# tinytouchbutton_v2_0_2.net
KiCad netlist of a schematic drawn in EAGLE
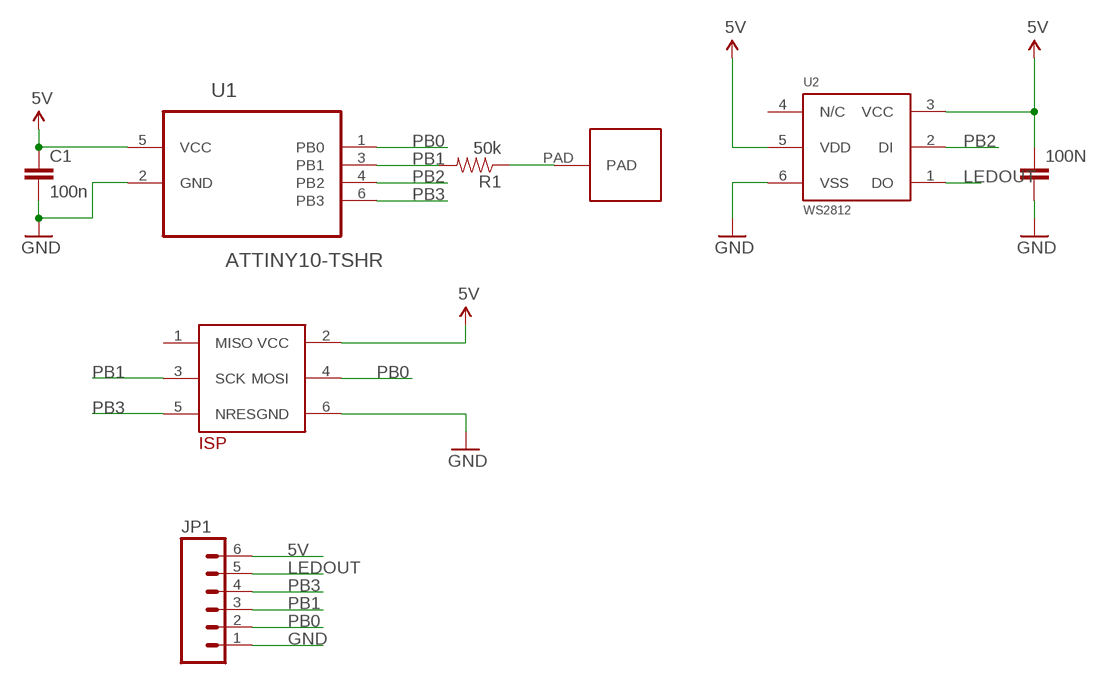
[diagram p0: schematic, sheet 1]

(export (version "E")
  (design (tool "Eeschema 10.0.6"))
  (components
    (comp (ref "100N")
      (value "CAP0805")
      (footprint "eagle-import:0805")
      (libsource (lib "eagle-import") (part "CAP0805"))
    )
    (comp (ref "C1")
      (value "100n")
      (footprint "eagle-import:0805")
      (libsource (lib "eagle-import") (part "CAP0805"))
    )
    (comp (ref "JP1")
      (value "M06SIP")
      (footprint "eagle-import:1X06")
      (libsource (lib "eagle-import") (part "M06SIP"))
    )
    (comp (ref "R1")
      (value "50k")
      (footprint "eagle-import:0805")
      (libsource (lib "eagle-import") (part "RESISTOR0805-RES"))
    )
    (comp (ref "U$1")
      (value "TB_ISPEDGE_2X3")
      (footprint "eagle-import:ISP_EDGE2X3")
      (libsource (lib "eagle-import") (part "TB_ISPEDGE_2X3"))
    )
    (comp (ref "U$2")
      (value "TB_TOUCH_0.5INCH")
      (footprint "eagle-import:TOUCH_ROUND0.5INCH")
      (libsource (lib "eagle-import") (part "TB_TOUCH_0.5INCH"))
    )
    (comp (ref "U1")
      (value "ATTINY10-TSHR")
      (footprint "eagle-import:SOT95P280X145-6N")
      (libsource (lib "eagle-import") (part "ATTINY10-TSHR"))
    )
    (comp (ref "U2")
      (value "WS2812")
      (footprint "eagle-import:PLCC6")
      (libsource (lib "eagle-import") (part "WS2812"))
    )
  )
  (nets
    (net (code "1") (name "/LEDOUT") (class "Default")
      (node (ref "JP1") (pin "5") (pinfunction "5_5") (pintype "passive"))
      (node (ref "U2") (pin "1") (pinfunction "DO_1") (pintype "output"))
    )
    (net (code "2") (name "/PB0") (class "Default")
      (node (ref "JP1") (pin "2") (pinfunction "2_2") (pintype "passive"))
      (node (ref "U$1") (pin "4") (pinfunction "MOSI_4") (pintype "bidirectional"))
      (node (ref "U1") (pin "1") (pinfunction "PB0_1") (pintype "bidirectional"))
    )
    (net (code "3") (name "/PB1") (class "Default")
      (node (ref "JP1") (pin "3") (pinfunction "3_3") (pintype "passive"))
      (node (ref "R1") (pin "2") (pinfunction "2_2") (pintype "passive"))
      (node (ref "U$1") (pin "3") (pinfunction "SCK_3") (pintype "bidirectional"))
      (node (ref "U1") (pin "3") (pinfunction "PB1_3") (pintype "bidirectional"))
    )
    (net (code "4") (name "/PB2") (class "Default")
      (node (ref "U1") (pin "4") (pinfunction "PB2_4") (pintype "bidirectional"))
      (node (ref "U2") (pin "2") (pinfunction "DI_2") (pintype "input"))
    )
    (net (code "5") (name "/PB3") (class "Default")
      (node (ref "JP1") (pin "4") (pinfunction "4_4") (pintype "passive"))
      (node (ref "U$1") (pin "5") (pinfunction "NRES_5") (pintype "bidirectional"))
      (node (ref "U1") (pin "6") (pinfunction "PB3_6") (pintype "bidirectional"))
    )
    (net (code "6") (name "5V") (class "Default")
      (node (ref "100N") (pin "1") (pinfunction "1_1") (pintype "passive"))
      (node (ref "C1") (pin "1") (pinfunction "1_1") (pintype "passive"))
      (node (ref "JP1") (pin "6") (pinfunction "6_6") (pintype "passive"))
      (node (ref "U$1") (pin "2") (pinfunction "VCC_2") (pintype "bidirectional"))
      (node (ref "U1") (pin "5") (pinfunction "VCC_5") (pintype "power_in"))
      (node (ref "U2") (pin "3") (pinfunction "VCC_3") (pintype "power_in"))
      (node (ref "U2") (pin "5") (pinfunction "VDD_5") (pintype "power_in"))
    )
    (net (code "7") (name "GND") (class "Default")
      (node (ref "100N") (pin "2") (pinfunction "2_2") (pintype "passive"))
      (node (ref "C1") (pin "2") (pinfunction "2_2") (pintype "passive"))
      (node (ref "JP1") (pin "1") (pinfunction "1_1") (pintype "passive"))
      (node (ref "U$1") (pin "6") (pinfunction "GND_6") (pintype "bidirectional"))
      (node (ref "U1") (pin "2") (pinfunction "GND_2") (pintype "passive"))
      (node (ref "U2") (pin "6") (pinfunction "VSS_6") (pintype "power_in"))
    )
    (net (code "8") (name "Net-(R1-Pad1)") (class "Default")
      (node (ref "R1") (pin "1") (pinfunction "1_1") (pintype "passive"))
      (node (ref "U$2") (pin "PAD") (pinfunction "PAD_PAD") (pintype "bidirectional"))
    )
    (net (code "9") (name "unconnected-(U$1-MISO-Pad1)") (class "Default")
      (node (ref "U$1") (pin "1") (pinfunction "MISO_1") (pintype "bidirectional"))
    )
    (net (code "10") (name "unconnected-(U2-N{slash}C-Pad4)") (class "Default")
      (node (ref "U2") (pin "4") (pinfunction "N/C_4") (pintype "bidirectional"))
    )
  )
)
